# LED_base_right.net
KiCad netlist of a schematic drawn in EAGLE
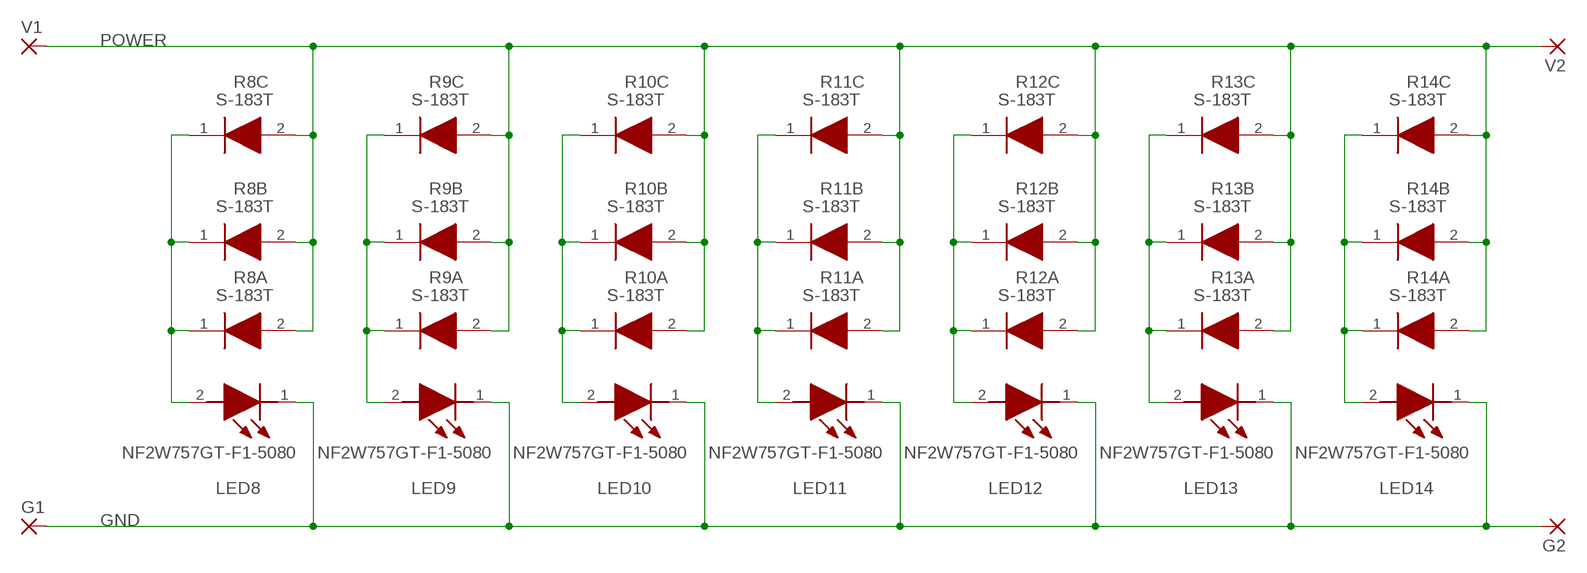
[diagram p0: schematic, sheet 1]

(export (version "E")
  (design (tool "Eeschema 10.0.6"))
  (components
    (comp (ref "G1")
      (value "SMD_HALF")
      (footprint "eagle-import:SMD1.75-2.5")
      (libsource (lib "eagle-import") (part "SMD_HALF"))
    )
    (comp (ref "G2")
      (value "SMD_FULL")
      (footprint "eagle-import:SMD3.5-2.5")
      (libsource (lib "eagle-import") (part "SMD_FULL"))
    )
    (comp (ref "LED8")
      (value "NF2W757GT-F1-5080")
      (footprint "eagle-import:NF2W757DRTX")
      (fields (field (name "RS_PART_NUMBER") "1372170"))
      (libsource (lib "eagle-import") (part "NF2W757GT-F1-5080"))
    )
    (comp (ref "LED9")
      (value "NF2W757GT-F1-5080")
      (footprint "eagle-import:NF2W757DRTX")
      (fields (field (name "RS_PART_NUMBER") "1372170"))
      (libsource (lib "eagle-import") (part "NF2W757GT-F1-5080"))
    )
    (comp (ref "LED10")
      (value "NF2W757GT-F1-5080")
      (footprint "eagle-import:NF2W757DRTX")
      (fields (field (name "RS_PART_NUMBER") "1372170"))
      (libsource (lib "eagle-import") (part "NF2W757GT-F1-5080"))
    )
    (comp (ref "LED11")
      (value "NF2W757GT-F1-5080")
      (footprint "eagle-import:NF2W757DRTX")
      (fields (field (name "RS_PART_NUMBER") "1372170"))
      (libsource (lib "eagle-import") (part "NF2W757GT-F1-5080"))
    )
    (comp (ref "LED12")
      (value "NF2W757GT-F1-5080")
      (footprint "eagle-import:NF2W757DRTX")
      (fields (field (name "RS_PART_NUMBER") "1372170"))
      (libsource (lib "eagle-import") (part "NF2W757GT-F1-5080"))
    )
    (comp (ref "LED13")
      (value "NF2W757GT-F1-5080")
      (footprint "eagle-import:NF2W757DRTX")
      (fields (field (name "RS_PART_NUMBER") "1372170"))
      (libsource (lib "eagle-import") (part "NF2W757GT-F1-5080"))
    )
    (comp (ref "LED14")
      (value "NF2W757GT-F1-5080")
      (footprint "eagle-import:NF2W757DRTX")
      (fields (field (name "RS_PART_NUMBER") "1372170"))
      (libsource (lib "eagle-import") (part "NF2W757GT-F1-5080"))
    )
    (comp (ref "R8A")
      (value "S-183T")
      (footprint "eagle-import:SODFL3516X70NX")
      (fields (field (name "MOUSER_PART_NUMBER") "954-S-183T"))
      (libsource (lib "eagle-import") (part "S-183T"))
    )
    (comp (ref "R8B")
      (value "S-183T")
      (footprint "eagle-import:SODFL3516X70NX")
      (fields (field (name "MOUSER_PART_NUMBER") "954-S-183T"))
      (libsource (lib "eagle-import") (part "S-183T"))
    )
    (comp (ref "R8C")
      (value "S-183T")
      (footprint "eagle-import:SODFL3516X70NX")
      (fields (field (name "MOUSER_PART_NUMBER") "954-S-183T"))
      (libsource (lib "eagle-import") (part "S-183T"))
    )
    (comp (ref "R9A")
      (value "S-183T")
      (footprint "eagle-import:SODFL3516X70NX")
      (fields (field (name "MOUSER_PART_NUMBER") "954-S-183T"))
      (libsource (lib "eagle-import") (part "S-183T"))
    )
    (comp (ref "R9B")
      (value "S-183T")
      (footprint "eagle-import:SODFL3516X70NX")
      (fields (field (name "MOUSER_PART_NUMBER") "954-S-183T"))
      (libsource (lib "eagle-import") (part "S-183T"))
    )
    (comp (ref "R9C")
      (value "S-183T")
      (footprint "eagle-import:SODFL3516X70NX")
      (fields (field (name "MOUSER_PART_NUMBER") "954-S-183T"))
      (libsource (lib "eagle-import") (part "S-183T"))
    )
    (comp (ref "R10A")
      (value "S-183T")
      (footprint "eagle-import:SODFL3516X70NX")
      (fields (field (name "MOUSER_PART_NUMBER") "954-S-183T"))
      (libsource (lib "eagle-import") (part "S-183T"))
    )
    (comp (ref "R10B")
      (value "S-183T")
      (footprint "eagle-import:SODFL3516X70NX")
      (fields (field (name "MOUSER_PART_NUMBER") "954-S-183T"))
      (libsource (lib "eagle-import") (part "S-183T"))
    )
    (comp (ref "R10C")
      (value "S-183T")
      (footprint "eagle-import:SODFL3516X70NX")
      (fields (field (name "MOUSER_PART_NUMBER") "954-S-183T"))
      (libsource (lib "eagle-import") (part "S-183T"))
    )
    (comp (ref "R11A")
      (value "S-183T")
      (footprint "eagle-import:SODFL3516X70NX")
      (fields (field (name "MOUSER_PART_NUMBER") "954-S-183T"))
      (libsource (lib "eagle-import") (part "S-183T"))
    )
    (comp (ref "R11B")
      (value "S-183T")
      (footprint "eagle-import:SODFL3516X70NX")
      (fields (field (name "MOUSER_PART_NUMBER") "954-S-183T"))
      (libsource (lib "eagle-import") (part "S-183T"))
    )
    (comp (ref "R11C")
      (value "S-183T")
      (footprint "eagle-import:SODFL3516X70NX")
      (fields (field (name "MOUSER_PART_NUMBER") "954-S-183T"))
      (libsource (lib "eagle-import") (part "S-183T"))
    )
    (comp (ref "R12A")
      (value "S-183T")
      (footprint "eagle-import:SODFL3516X70NX")
      (fields (field (name "MOUSER_PART_NUMBER") "954-S-183T"))
      (libsource (lib "eagle-import") (part "S-183T"))
    )
    (comp (ref "R12B")
      (value "S-183T")
      (footprint "eagle-import:SODFL3516X70NX")
      (fields (field (name "MOUSER_PART_NUMBER") "954-S-183T"))
      (libsource (lib "eagle-import") (part "S-183T"))
    )
    (comp (ref "R12C")
      (value "S-183T")
      (footprint "eagle-import:SODFL3516X70NX")
      (fields (field (name "MOUSER_PART_NUMBER") "954-S-183T"))
      (libsource (lib "eagle-import") (part "S-183T"))
    )
    (comp (ref "R13A")
      (value "S-183T")
      (footprint "eagle-import:SODFL3516X70NX")
      (fields (field (name "MOUSER_PART_NUMBER") "954-S-183T"))
      (libsource (lib "eagle-import") (part "S-183T"))
    )
    (comp (ref "R13B")
      (value "S-183T")
      (footprint "eagle-import:SODFL3516X70NX")
      (fields (field (name "MOUSER_PART_NUMBER") "954-S-183T"))
      (libsource (lib "eagle-import") (part "S-183T"))
    )
    (comp (ref "R13C")
      (value "S-183T")
      (footprint "eagle-import:SODFL3516X70NX")
      (fields (field (name "MOUSER_PART_NUMBER") "954-S-183T"))
      (libsource (lib "eagle-import") (part "S-183T"))
    )
    (comp (ref "R14A")
      (value "S-183T")
      (footprint "eagle-import:SODFL3516X70NX")
      (fields (field (name "MOUSER_PART_NUMBER") "954-S-183T"))
      (libsource (lib "eagle-import") (part "S-183T"))
    )
    (comp (ref "R14B")
      (value "S-183T")
      (footprint "eagle-import:SODFL3516X70NX")
      (fields (field (name "MOUSER_PART_NUMBER") "954-S-183T"))
      (libsource (lib "eagle-import") (part "S-183T"))
    )
    (comp (ref "R14C")
      (value "S-183T")
      (footprint "eagle-import:SODFL3516X70NX")
      (fields (field (name "MOUSER_PART_NUMBER") "954-S-183T"))
      (libsource (lib "eagle-import") (part "S-183T"))
    )
    (comp (ref "V1")
      (value "SMD_HALF")
      (footprint "eagle-import:SMD1.75-2.5")
      (libsource (lib "eagle-import") (part "SMD_HALF"))
    )
    (comp (ref "V2")
      (value "SMD_FULL")
      (footprint "eagle-import:SMD3.5-2.5")
      (libsource (lib "eagle-import") (part "SMD_FULL"))
    )
  )
  (nets
    (net (code "1") (name "/GND") (class "Default")
      (node (ref "G1") (pin "1") (pinfunction "P_1") (pintype "passive"))
      (node (ref "G2") (pin "1") (pinfunction "P_1") (pintype "passive"))
      (node (ref "LED10") (pin "1") (pinfunction "K_1") (pintype "bidirectional"))
      (node (ref "LED11") (pin "1") (pinfunction "K_1") (pintype "bidirectional"))
      (node (ref "LED12") (pin "1") (pinfunction "K_1") (pintype "bidirectional"))
      (node (ref "LED13") (pin "1") (pinfunction "K_1") (pintype "bidirectional"))
      (node (ref "LED14") (pin "1") (pinfunction "K_1") (pintype "bidirectional"))
      (node (ref "LED8") (pin "1") (pinfunction "K_1") (pintype "bidirectional"))
      (node (ref "LED9") (pin "1") (pinfunction "K_1") (pintype "bidirectional"))
    )
    (net (code "2") (name "/POWER") (class "Default")
      (node (ref "R10A") (pin "2") (pinfunction "A_2") (pintype "bidirectional"))
      (node (ref "R10B") (pin "2") (pinfunction "A_2") (pintype "bidirectional"))
      (node (ref "R10C") (pin "2") (pinfunction "A_2") (pintype "bidirectional"))
      (node (ref "R11A") (pin "2") (pinfunction "A_2") (pintype "bidirectional"))
      (node (ref "R11B") (pin "2") (pinfunction "A_2") (pintype "bidirectional"))
      (node (ref "R11C") (pin "2") (pinfunction "A_2") (pintype "bidirectional"))
      (node (ref "R12A") (pin "2") (pinfunction "A_2") (pintype "bidirectional"))
      (node (ref "R12B") (pin "2") (pinfunction "A_2") (pintype "bidirectional"))
      (node (ref "R12C") (pin "2") (pinfunction "A_2") (pintype "bidirectional"))
      (node (ref "R13A") (pin "2") (pinfunction "A_2") (pintype "bidirectional"))
      (node (ref "R13B") (pin "2") (pinfunction "A_2") (pintype "bidirectional"))
      (node (ref "R13C") (pin "2") (pinfunction "A_2") (pintype "bidirectional"))
      (node (ref "R14A") (pin "2") (pinfunction "A_2") (pintype "bidirectional"))
      (node (ref "R14B") (pin "2") (pinfunction "A_2") (pintype "bidirectional"))
      (node (ref "R14C") (pin "2") (pinfunction "A_2") (pintype "bidirectional"))
      (node (ref "R8A") (pin "2") (pinfunction "A_2") (pintype "bidirectional"))
      (node (ref "R8B") (pin "2") (pinfunction "A_2") (pintype "bidirectional"))
      (node (ref "R8C") (pin "2") (pinfunction "A_2") (pintype "bidirectional"))
      (node (ref "R9A") (pin "2") (pinfunction "A_2") (pintype "bidirectional"))
      (node (ref "R9B") (pin "2") (pinfunction "A_2") (pintype "bidirectional"))
      (node (ref "R9C") (pin "2") (pinfunction "A_2") (pintype "bidirectional"))
      (node (ref "V1") (pin "1") (pinfunction "P_1") (pintype "passive"))
      (node (ref "V2") (pin "1") (pinfunction "P_1") (pintype "passive"))
    )
    (net (code "3") (name "Net-(LED8-A)") (class "Default")
      (node (ref "LED8") (pin "2") (pinfunction "A_2") (pintype "bidirectional"))
      (node (ref "R8A") (pin "1") (pinfunction "K_1") (pintype "bidirectional"))
      (node (ref "R8B") (pin "1") (pinfunction "K_1") (pintype "bidirectional"))
      (node (ref "R8C") (pin "1") (pinfunction "K_1") (pintype "bidirectional"))
    )
    (net (code "4") (name "Net-(LED9-A)") (class "Default")
      (node (ref "LED9") (pin "2") (pinfunction "A_2") (pintype "bidirectional"))
      (node (ref "R9A") (pin "1") (pinfunction "K_1") (pintype "bidirectional"))
      (node (ref "R9B") (pin "1") (pinfunction "K_1") (pintype "bidirectional"))
      (node (ref "R9C") (pin "1") (pinfunction "K_1") (pintype "bidirectional"))
    )
    (net (code "5") (name "Net-(LED10-A)") (class "Default")
      (node (ref "LED10") (pin "2") (pinfunction "A_2") (pintype "bidirectional"))
      (node (ref "R10A") (pin "1") (pinfunction "K_1") (pintype "bidirectional"))
      (node (ref "R10B") (pin "1") (pinfunction "K_1") (pintype "bidirectional"))
      (node (ref "R10C") (pin "1") (pinfunction "K_1") (pintype "bidirectional"))
    )
    (net (code "6") (name "Net-(LED11-A)") (class "Default")
      (node (ref "LED11") (pin "2") (pinfunction "A_2") (pintype "bidirectional"))
      (node (ref "R11A") (pin "1") (pinfunction "K_1") (pintype "bidirectional"))
      (node (ref "R11B") (pin "1") (pinfunction "K_1") (pintype "bidirectional"))
      (node (ref "R11C") (pin "1") (pinfunction "K_1") (pintype "bidirectional"))
    )
    (net (code "7") (name "Net-(LED12-A)") (class "Default")
      (node (ref "LED12") (pin "2") (pinfunction "A_2") (pintype "bidirectional"))
      (node (ref "R12A") (pin "1") (pinfunction "K_1") (pintype "bidirectional"))
      (node (ref "R12B") (pin "1") (pinfunction "K_1") (pintype "bidirectional"))
      (node (ref "R12C") (pin "1") (pinfunction "K_1") (pintype "bidirectional"))
    )
    (net (code "8") (name "Net-(LED13-A)") (class "Default")
      (node (ref "LED13") (pin "2") (pinfunction "A_2") (pintype "bidirectional"))
      (node (ref "R13A") (pin "1") (pinfunction "K_1") (pintype "bidirectional"))
      (node (ref "R13B") (pin "1") (pinfunction "K_1") (pintype "bidirectional"))
      (node (ref "R13C") (pin "1") (pinfunction "K_1") (pintype "bidirectional"))
    )
    (net (code "9") (name "Net-(LED14-A)") (class "Default")
      (node (ref "LED14") (pin "2") (pinfunction "A_2") (pintype "bidirectional"))
      (node (ref "R14A") (pin "1") (pinfunction "K_1") (pintype "bidirectional"))
      (node (ref "R14B") (pin "1") (pinfunction "K_1") (pintype "bidirectional"))
      (node (ref "R14C") (pin "1") (pinfunction "K_1") (pintype "bidirectional"))
    )
  )
)
